# ProDoc_P1_2026-04-07.net
KiCad netlist of a schematic drawn in EasyEDA Pro
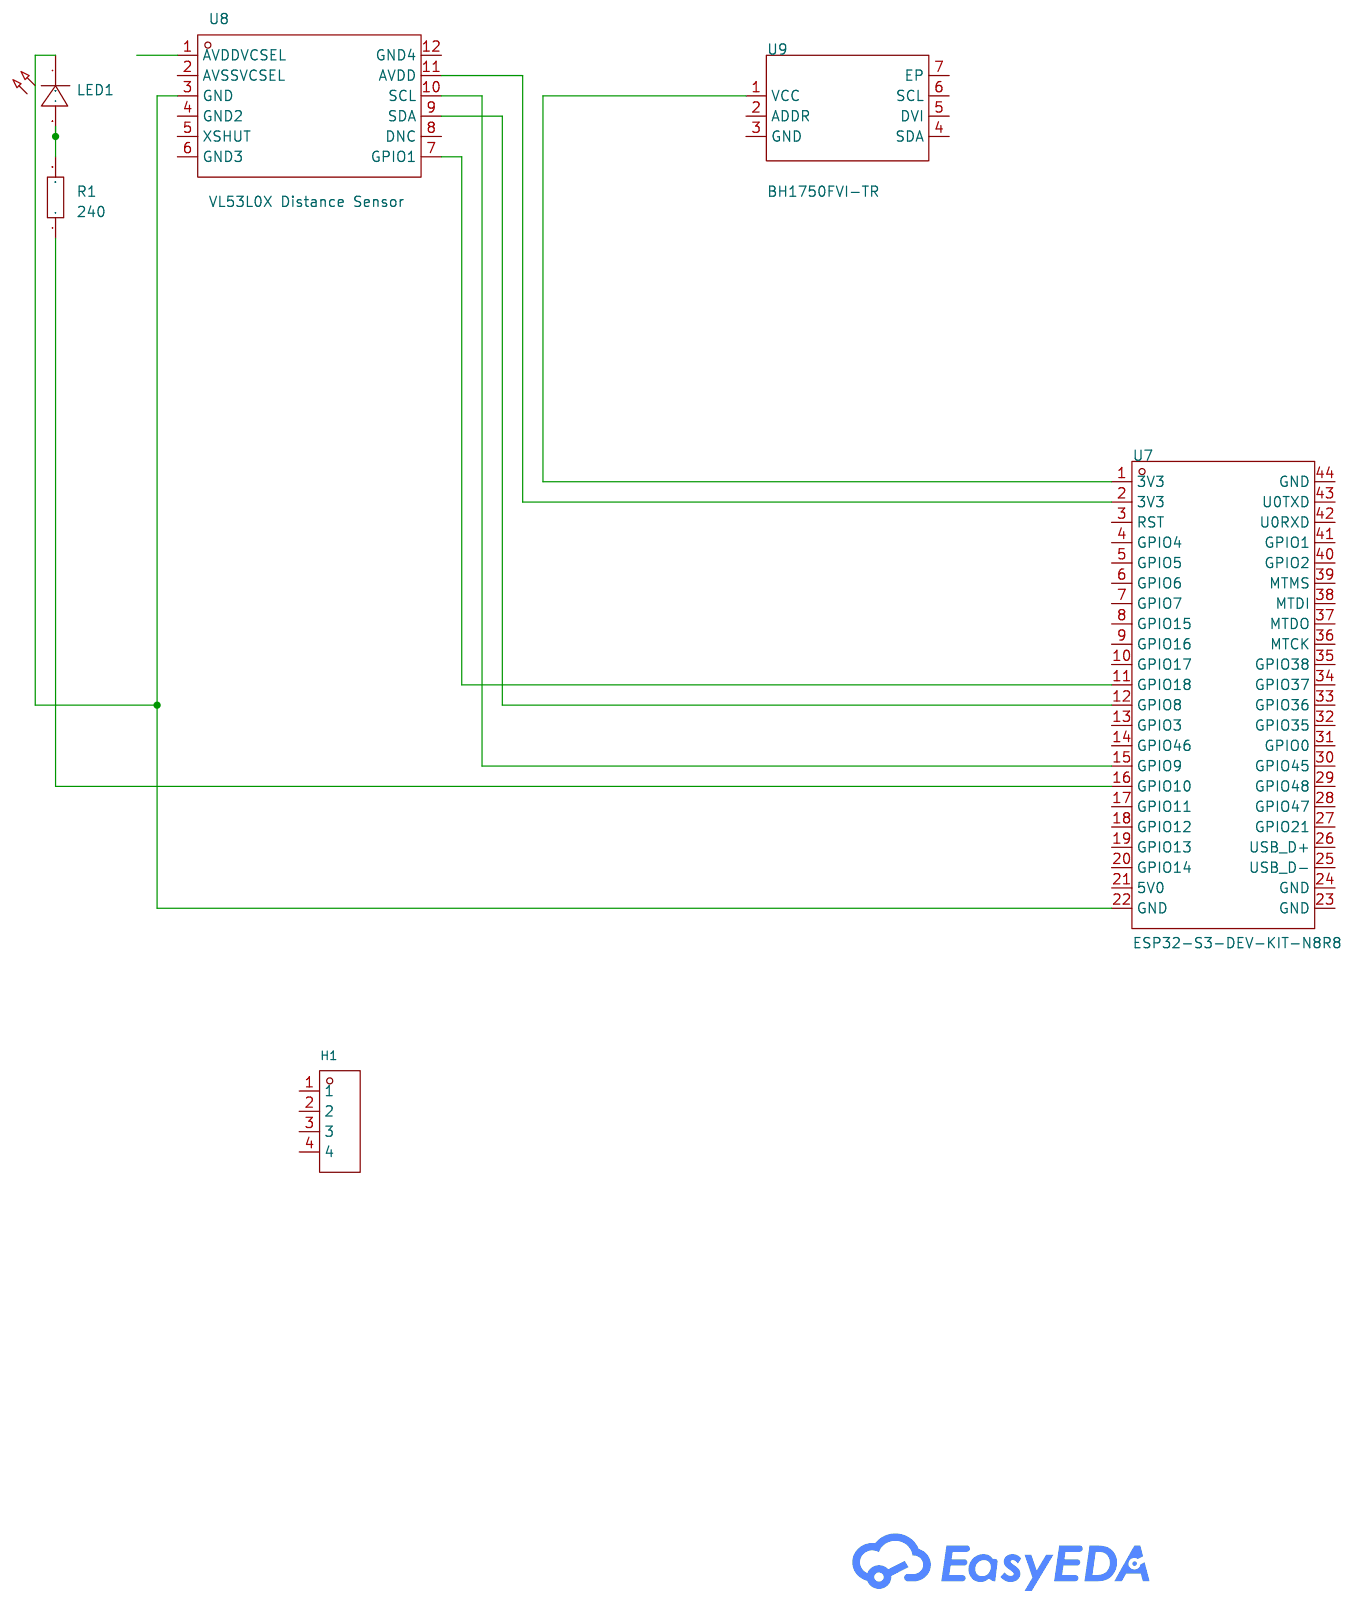
[diagram p0: schematic sheet]

(export (version "E")
  (design (tool "Eeschema 10.0.6"))
  (components
    (comp (ref "H1")
      (value "~")
      (footprint "easyedapro:HDR-TH_4P-P2.54-V-F")
      (libsource (lib "easyedapro") (part "2.54-1*4P母"))
    )
    (comp (ref "LED1")
      (value "~")
      (footprint "easyedapro:LED0603-RD_GREEN")
      (libsource (lib "easyedapro") (part "LED_G"))
    )
    (comp (ref "R1") (value "10K") (footprint "easyedapro:R0603") (libsource (lib "easyedapro") (part "Res")))
    (comp (ref "U7")
      (value "ESP32-S3-DEV-KIT-N8R8")
      (footprint "easyedapro:COMM-TH_L63.3-W25.4-P2.54-LS22.86")
      (libsource (lib "easyedapro") (part "ESP32-S3-DEV-KIT-N8R8"))
    )
    (comp (ref "U8")
      (value "VL53L0X Distance Sensor")
      (footprint "easyedapro:SENSOR-SMD_12P-L4.4-W2.4_VL53L0X")
      (fields (field (name "Manufacturer") "Waveshare(微雪电子)"))
      (libsource (lib "easyedapro") (part "VL53L0X DISTANCE SENSOR"))
    )
    (comp (ref "U9")
      (value "BH1750FVI-TR")
      (footprint "easyedapro:WSOF-6_L2.6-W1.6-P0.50-TL-EP")
      (fields (field (name "Manufacturer") "ROHM(罗姆)"))
      (libsource (lib "easyedapro") (part "BH1750FVI-TR"))
    )
  )
  (nets
    (net (code "1") (name "Net-(LED1-A)") (class "Default")
      (node (ref "LED1") (pin "2") (pinfunction "A_2") (pintype "input"))
      (node (ref "R1") (pin "2") (pinfunction "2_2") (pintype "input"))
    )
    (net (code "2") (name "Net-(LED1-C)") (class "Default")
      (node (ref "LED1") (pin "1") (pinfunction "C_1") (pintype "input"))
      (node (ref "U7") (pin "22") (pinfunction "GND_22") (pintype "unspecified"))
      (node (ref "U8") (pin "3") (pinfunction "GND_3") (pintype "unspecified"))
    )
    (net (code "3") (name "Net-(U7-GPIO8)") (class "Default")
      (node (ref "U7") (pin "12") (pinfunction "GPIO8_12") (pintype "unspecified"))
      (node (ref "U8") (pin "9") (pinfunction "SDA_9") (pintype "unspecified"))
    )
    (net (code "4") (name "Net-(U7-GPIO9)") (class "Default")
      (node (ref "U7") (pin "15") (pinfunction "GPIO9_15") (pintype "unspecified"))
      (node (ref "U8") (pin "10") (pinfunction "SCL_10") (pintype "unspecified"))
    )
    (net (code "5") (name "Net-(U7-GPIO10)") (class "Default")
      (node (ref "R1") (pin "1") (pinfunction "1_1") (pintype "input"))
      (node (ref "U7") (pin "16") (pinfunction "GPIO10_16") (pintype "unspecified"))
    )
    (net (code "6") (name "Net-(U7-GPIO18)") (class "Default")
      (node (ref "U7") (pin "11") (pinfunction "GPIO18_11") (pintype "unspecified"))
      (node (ref "U8") (pin "7") (pinfunction "GPIO1_7") (pintype "unspecified"))
    )
    (net (code "7") (name "Net-(U8-AVDD)") (class "Default")
      (node (ref "U7") (pin "2") (pinfunction "3V3_2") (pintype "unspecified"))
      (node (ref "U8") (pin "11") (pinfunction "AVDD_11") (pintype "unspecified"))
    )
    (net (code "8") (name "Net-(U9-VCC)") (class "Default")
      (node (ref "U7") (pin "1") (pinfunction "3V3_1") (pintype "unspecified"))
      (node (ref "U9") (pin "1") (pinfunction "VCC_1") (pintype "unspecified"))
    )
    (net (code "9") (name "unconnected-(H1-Pad1)") (class "Default")
      (node (ref "H1") (pin "1") (pinfunction "1_1") (pintype "input"))
    )
    (net (code "10") (name "unconnected-(H1-Pad2)") (class "Default")
      (node (ref "H1") (pin "2") (pinfunction "2_2") (pintype "input"))
    )
    (net (code "11") (name "unconnected-(H1-Pad3)") (class "Default")
      (node (ref "H1") (pin "3") (pinfunction "3_3") (pintype "input"))
    )
    (net (code "12") (name "unconnected-(H1-Pad4)") (class "Default")
      (node (ref "H1") (pin "4") (pinfunction "4_4") (pintype "input"))
    )
    (net (code "13") (name "unconnected-(U7-5V0-Pad21)") (class "Default")
      (node (ref "U7") (pin "21") (pinfunction "5V0_21") (pintype "unspecified"))
    )
    (net (code "14") (name "unconnected-(U7-GND-Pad23)") (class "Default")
      (node (ref "U7") (pin "23") (pinfunction "GND_23") (pintype "unspecified"))
    )
    (net (code "15") (name "unconnected-(U7-GND-Pad24)") (class "Default")
      (node (ref "U7") (pin "24") (pinfunction "GND_24") (pintype "unspecified"))
    )
    (net (code "16") (name "unconnected-(U7-GND-Pad44)") (class "Default")
      (node (ref "U7") (pin "44") (pinfunction "GND_44") (pintype "unspecified"))
    )
    (net (code "17") (name "unconnected-(U7-GPIO0-Pad31)") (class "Default")
      (node (ref "U7") (pin "31") (pinfunction "GPIO0_31") (pintype "unspecified"))
    )
    (net (code "18") (name "unconnected-(U7-GPIO1-Pad41)") (class "Default")
      (node (ref "U7") (pin "41") (pinfunction "GPIO1_41") (pintype "unspecified"))
    )
    (net (code "19") (name "unconnected-(U7-GPIO2-Pad40)") (class "Default")
      (node (ref "U7") (pin "40") (pinfunction "GPIO2_40") (pintype "unspecified"))
    )
    (net (code "20") (name "unconnected-(U7-GPIO3-Pad13)") (class "Default")
      (node (ref "U7") (pin "13") (pinfunction "GPIO3_13") (pintype "unspecified"))
    )
    (net (code "21") (name "unconnected-(U7-GPIO4-Pad4)") (class "Default")
      (node (ref "U7") (pin "4") (pinfunction "GPIO4_4") (pintype "unspecified"))
    )
    (net (code "22") (name "unconnected-(U7-GPIO5-Pad5)") (class "Default")
      (node (ref "U7") (pin "5") (pinfunction "GPIO5_5") (pintype "unspecified"))
    )
    (net (code "23") (name "unconnected-(U7-GPIO6-Pad6)") (class "Default")
      (node (ref "U7") (pin "6") (pinfunction "GPIO6_6") (pintype "unspecified"))
    )
    (net (code "24") (name "unconnected-(U7-GPIO7-Pad7)") (class "Default")
      (node (ref "U7") (pin "7") (pinfunction "GPIO7_7") (pintype "unspecified"))
    )
    (net (code "25") (name "unconnected-(U7-GPIO11-Pad17)") (class "Default")
      (node (ref "U7") (pin "17") (pinfunction "GPIO11_17") (pintype "unspecified"))
    )
    (net (code "26") (name "unconnected-(U7-GPIO12-Pad18)") (class "Default")
      (node (ref "U7") (pin "18") (pinfunction "GPIO12_18") (pintype "unspecified"))
    )
    (net (code "27") (name "unconnected-(U7-GPIO13-Pad19)") (class "Default")
      (node (ref "U7") (pin "19") (pinfunction "GPIO13_19") (pintype "unspecified"))
    )
    (net (code "28") (name "unconnected-(U7-GPIO14-Pad20)") (class "Default")
      (node (ref "U7") (pin "20") (pinfunction "GPIO14_20") (pintype "unspecified"))
    )
    (net (code "29") (name "unconnected-(U7-GPIO15-Pad8)") (class "Default")
      (node (ref "U7") (pin "8") (pinfunction "GPIO15_8") (pintype "unspecified"))
    )
    (net (code "30") (name "unconnected-(U7-GPIO16-Pad9)") (class "Default")
      (node (ref "U7") (pin "9") (pinfunction "GPIO16_9") (pintype "unspecified"))
    )
    (net (code "31") (name "unconnected-(U7-GPIO17-Pad10)") (class "Default")
      (node (ref "U7") (pin "10") (pinfunction "GPIO17_10") (pintype "unspecified"))
    )
    (net (code "32") (name "unconnected-(U7-GPIO21-Pad27)") (class "Default")
      (node (ref "U7") (pin "27") (pinfunction "GPIO21_27") (pintype "unspecified"))
    )
    (net (code "33") (name "unconnected-(U7-GPIO35-Pad32)") (class "Default")
      (node (ref "U7") (pin "32") (pinfunction "GPIO35_32") (pintype "unspecified"))
    )
    (net (code "34") (name "unconnected-(U7-GPIO36-Pad33)") (class "Default")
      (node (ref "U7") (pin "33") (pinfunction "GPIO36_33") (pintype "unspecified"))
    )
    (net (code "35") (name "unconnected-(U7-GPIO37-Pad34)") (class "Default")
      (node (ref "U7") (pin "34") (pinfunction "GPIO37_34") (pintype "unspecified"))
    )
    (net (code "36") (name "unconnected-(U7-GPIO38-Pad35)") (class "Default")
      (node (ref "U7") (pin "35") (pinfunction "GPIO38_35") (pintype "unspecified"))
    )
    (net (code "37") (name "unconnected-(U7-GPIO45-Pad30)") (class "Default")
      (node (ref "U7") (pin "30") (pinfunction "GPIO45_30") (pintype "unspecified"))
    )
    (net (code "38") (name "unconnected-(U7-GPIO46-Pad14)") (class "Default")
      (node (ref "U7") (pin "14") (pinfunction "GPIO46_14") (pintype "unspecified"))
    )
    (net (code "39") (name "unconnected-(U7-GPIO47-Pad28)") (class "Default")
      (node (ref "U7") (pin "28") (pinfunction "GPIO47_28") (pintype "unspecified"))
    )
    (net (code "40") (name "unconnected-(U7-GPIO48-Pad29)") (class "Default")
      (node (ref "U7") (pin "29") (pinfunction "GPIO48_29") (pintype "unspecified"))
    )
    (net (code "41") (name "unconnected-(U7-MTCK-Pad36)") (class "Default")
      (node (ref "U7") (pin "36") (pinfunction "MTCK_36") (pintype "unspecified"))
    )
    (net (code "42") (name "unconnected-(U7-MTDI-Pad38)") (class "Default")
      (node (ref "U7") (pin "38") (pinfunction "MTDI_38") (pintype "unspecified"))
    )
    (net (code "43") (name "unconnected-(U7-MTDO-Pad37)") (class "Default")
      (node (ref "U7") (pin "37") (pinfunction "MTDO_37") (pintype "unspecified"))
    )
    (net (code "44") (name "unconnected-(U7-MTMS-Pad39)") (class "Default")
      (node (ref "U7") (pin "39") (pinfunction "MTMS_39") (pintype "unspecified"))
    )
    (net (code "45") (name "unconnected-(U7-RST-Pad3)") (class "Default")
      (node (ref "U7") (pin "3") (pinfunction "RST_3") (pintype "unspecified"))
    )
    (net (code "46") (name "unconnected-(U7-U0RXD-Pad42)") (class "Default")
      (node (ref "U7") (pin "42") (pinfunction "U0RXD_42") (pintype "unspecified"))
    )
    (net (code "47") (name "unconnected-(U7-U0TXD-Pad43)") (class "Default")
      (node (ref "U7") (pin "43") (pinfunction "U0TXD_43") (pintype "unspecified"))
    )
    (net (code "48") (name "unconnected-(U7-USB_D+-Pad26)") (class "Default")
      (node (ref "U7") (pin "26") (pinfunction "USB_D+_26") (pintype "unspecified"))
    )
    (net (code "49") (name "unconnected-(U7-USB_D--Pad25)") (class "Default")
      (node (ref "U7") (pin "25") (pinfunction "USB_D-_25") (pintype "unspecified"))
    )
    (net (code "50") (name "unconnected-(U8-AVDDVCSEL-Pad1)") (class "Default")
      (node (ref "U8") (pin "1") (pinfunction "AVDDVCSEL_1") (pintype "unspecified"))
    )
    (net (code "51") (name "unconnected-(U8-AVSSVCSEL-Pad2)") (class "Default")
      (node (ref "U8") (pin "2") (pinfunction "AVSSVCSEL_2") (pintype "unspecified"))
    )
    (net (code "52") (name "unconnected-(U8-DNC-Pad8)") (class "Default")
      (node (ref "U8") (pin "8") (pinfunction "DNC_8") (pintype "unspecified"))
    )
    (net (code "53") (name "unconnected-(U8-GND2-Pad4)") (class "Default")
      (node (ref "U8") (pin "4") (pinfunction "GND2_4") (pintype "unspecified"))
    )
    (net (code "54") (name "unconnected-(U8-GND3-Pad6)") (class "Default")
      (node (ref "U8") (pin "6") (pinfunction "GND3_6") (pintype "unspecified"))
    )
    (net (code "55") (name "unconnected-(U8-GND4-Pad12)") (class "Default")
      (node (ref "U8") (pin "12") (pinfunction "GND4_12") (pintype "unspecified"))
    )
    (net (code "56") (name "unconnected-(U8-XSHUT-Pad5)") (class "Default")
      (node (ref "U8") (pin "5") (pinfunction "XSHUT_5") (pintype "unspecified"))
    )
    (net (code "57") (name "unconnected-(U9-ADDR-Pad2)") (class "Default")
      (node (ref "U9") (pin "2") (pinfunction "ADDR_2") (pintype "unspecified"))
    )
    (net (code "58") (name "unconnected-(U9-DVI-Pad5)") (class "Default")
      (node (ref "U9") (pin "5") (pinfunction "DVI_5") (pintype "unspecified"))
    )
    (net (code "59") (name "unconnected-(U9-EP-Pad7)") (class "Default")
      (node (ref "U9") (pin "7") (pinfunction "EP_7") (pintype "unspecified"))
    )
    (net (code "60") (name "unconnected-(U9-GND-Pad3)") (class "Default")
      (node (ref "U9") (pin "3") (pinfunction "GND_3") (pintype "unspecified"))
    )
    (net (code "61") (name "unconnected-(U9-SCL-Pad6)") (class "Default")
      (node (ref "U9") (pin "6") (pinfunction "SCL_6") (pintype "unspecified"))
    )
    (net (code "62") (name "unconnected-(U9-SDA-Pad4)") (class "Default")
      (node (ref "U9") (pin "4") (pinfunction "SDA_4") (pintype "unspecified"))
    )
  )
)
